# ESP-MGMT.net
KiCad netlist of a schematic drawn in Altium Designer
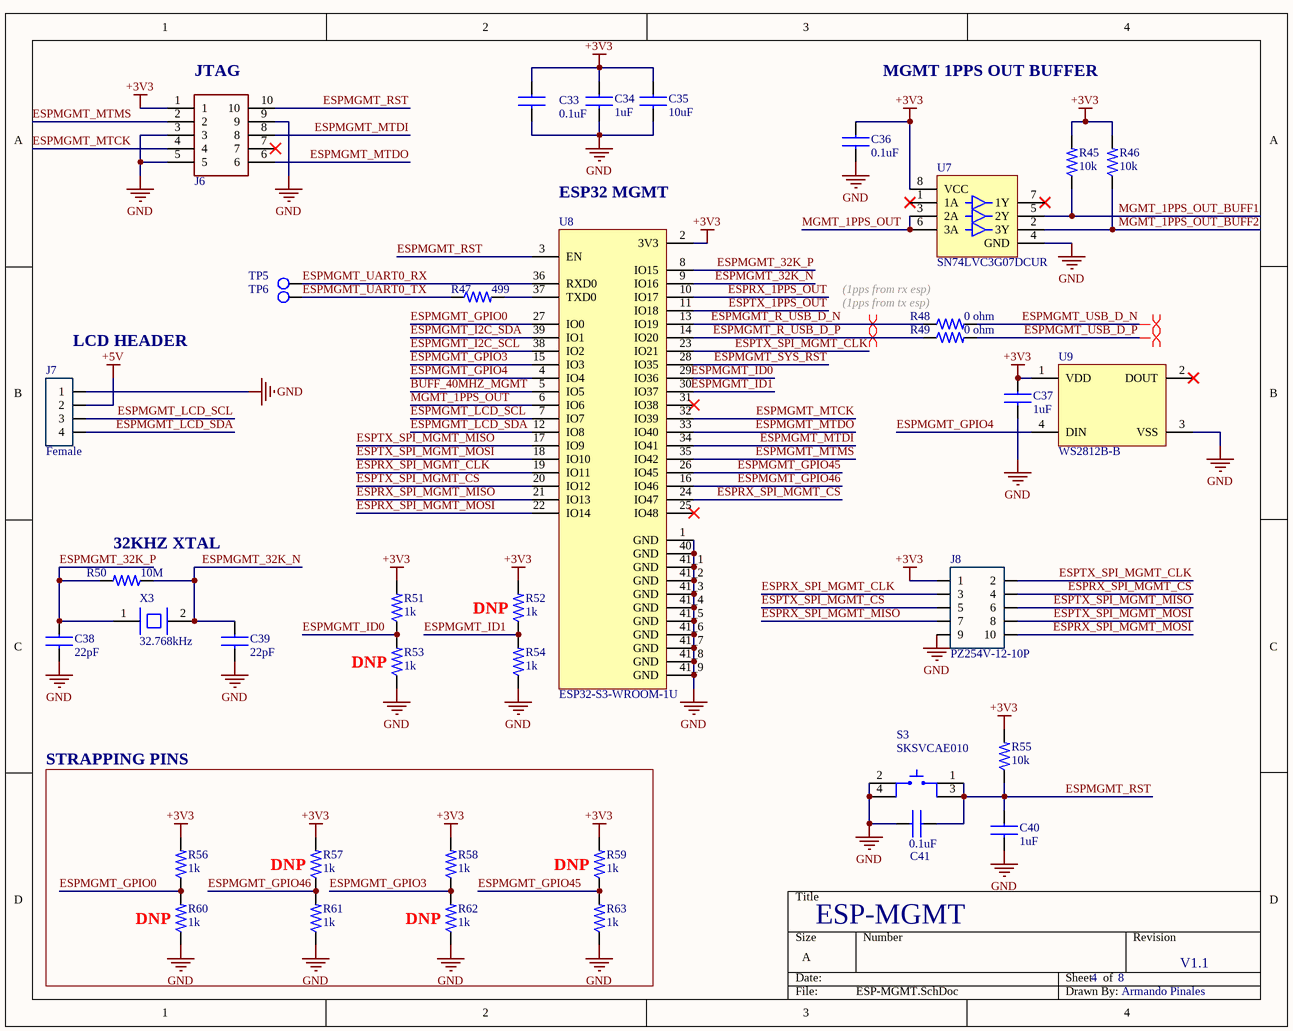
[diagram p0: ESP-MGMT.SchDoc]

(export (version "E")
  (design (tool "Eeschema 10.0.6"))
  (components
    (comp (ref "C33")
      (value "0.1uF")
      (footprint "CAP_0402")
      (description "Cap Ceramic 0.1uF 16V X7R 10% SMD 0402 125C Paper T/R")
      (fields
        (field (name "MANUFACTURER") "Murata")
        (field (name "MANUFACTURER PART NUMBER") "GCM155R71C104KA55J")
      )
      (libsource (lib "LotusSound") (part "CAP_GCM155R71C104KA55J"))
    )
    (comp (ref "C34")
      (value "1uF")
      (footprint "CAP_0402")
      (description "Cap Ceramic 1uF 25V X5R 10% SMD 0402 85°C Cardboard T/R")
      (fields
        (field (name "MANUFACTURER") "Samsung")
        (field (name "MANUFACTURER PART NUMBER") "CL05A105KA5NQNC")
      )
      (libsource (lib "LotusSound") (part "CAP_CL05A105KA5NQNC"))
    )
    (comp (ref "C35")
      (value "10uF")
      (footprint "CAP_0402")
      (description "Cap Ceramic 10uF 6.3V X5R 20% SMD 0402 85°C Paper T/R")
      (fields
        (field (name "MANUFACTURER") "Samsung")
        (field (name "MANUFACTURER PART NUMBER") "CL05A106MQ5NUNC")
      )
      (libsource (lib "LotusSound") (part "CAP_CL05A106MQ5NUNC"))
    )
    (comp (ref "C36")
      (value "0.1uF")
      (footprint "CAP_0402")
      (description "Cap Ceramic 0.1uF 16V X7R 10% SMD 0402 125C Paper T/R")
      (fields
        (field (name "MANUFACTURER") "Murata")
        (field (name "MANUFACTURER PART NUMBER") "GCM155R71C104KA55J")
      )
      (libsource (lib "LotusSound") (part "CAP_GCM155R71C104KA55J"))
    )
    (comp (ref "C37")
      (value "1uF")
      (footprint "CAP_0402")
      (description "Cap Ceramic 1uF 25V X5R 10% SMD 0402 85°C Cardboard T/R")
      (fields
        (field (name "MANUFACTURER") "Samsung")
        (field (name "MANUFACTURER PART NUMBER") "CL05A105KA5NQNC")
      )
      (libsource (lib "LotusSound") (part "CAP_CL05A105KA5NQNC"))
    )
    (comp (ref "C38")
      (value "22pF")
      (footprint "CAP_0402")
      (description "0402 22 pF 50 V ±5 % Tolerance NP0 SMT Multilayer Ceramic Capacitor")
      (fields
        (field (name "MANUFACTURER") "Yageo")
        (field (name "MANUFACTURER PART NUMBER") "CC0402JRNPO9BN220")
      )
      (libsource (lib "LotusSound") (part "CAP_CC0402JRNPO9BN220"))
    )
    (comp (ref "C39")
      (value "22pF")
      (footprint "CAP_0402")
      (description "0402 22 pF 50 V ±5 % Tolerance NP0 SMT Multilayer Ceramic Capacitor")
      (fields
        (field (name "MANUFACTURER") "Yageo")
        (field (name "MANUFACTURER PART NUMBER") "CC0402JRNPO9BN220")
      )
      (libsource (lib "LotusSound") (part "CAP_CC0402JRNPO9BN220"))
    )
    (comp (ref "C40")
      (value "1uF")
      (footprint "CAP_0402")
      (description "Cap Ceramic 1uF 25V X5R 10% SMD 0402 85°C Cardboard T/R")
      (fields
        (field (name "MANUFACTURER") "Samsung")
        (field (name "MANUFACTURER PART NUMBER") "CL05A105KA5NQNC")
      )
      (libsource (lib "LotusSound") (part "CAP_CL05A105KA5NQNC"))
    )
    (comp (ref "C41")
      (value "0.1uF")
      (footprint "CAP_0402")
      (description "Cap Ceramic 0.1uF 16V X7R 10% SMD 0402 125C Paper T/R")
      (fields
        (field (name "MANUFACTURER") "Murata")
        (field (name "MANUFACTURER PART NUMBER") "GCM155R71C104KA55J")
      )
      (libsource (lib "LotusSound") (part "CAP_GCM155R71C104KA55J"))
    )
    (comp (ref "J6")
      (value "CONN_TC2050-IDC")
      (footprint "CONN_TAG-CONNECT_TC2050-IDC")
      (description "Cbl Plug-Of-Nails 10-Pin w/Legs")
      (fields (field (name "MF") "{'manufacturer': u'Tag-Connect LLC'}") (field (name "MP") "TC2050-IDC"))
      (libsource (lib "LotusSound") (part "CONN_TC2050-IDC"))
    )
    (comp (ref "J7")
      (value "Female")
      (footprint "CONN_4_PIN_100MIL")
      (description "4 Position Header Connector 0.100\" (2.54mm) Through Hole Tin")
      (fields (field (name "DIGIKEY PART") "S7004-ND") (field (name "LCSC PART#") "DNP"))
      (libsource (lib "LotusSound") (part "CONN_4_PIN_FEMALE"))
    )
    (comp (ref "J8")
      (value "PZ254V-12-10P")
      (footprint "CONN_10_PIN_M_100MIL")
      (description "双排排针 间距2.54mm 10pin 直插")
      (fields (field (name "MANUFACTURER") "XFCN"))
      (libsource (lib "LotusSound") (part "CONN_10_PIN_MALE_PZ254V-12-10P"))
    )
    (comp (ref "R45")
      (value "10k")
      (footprint "RES_0402")
      (description "RES SMD 10K OHM 1% 1/16W 0402")
      (fields
        (field (name "MANUFACTURER") "Yageo")
        (field (name "MANUFACTURER PART NUMBER") "AC0402FR-0710KL")
      )
      (libsource (lib "LotusSound") (part "RES_AC0402FR-0710KL"))
    )
    (comp (ref "R46")
      (value "10k")
      (footprint "RES_0402")
      (description "RES SMD 10K OHM 1% 1/16W 0402")
      (fields
        (field (name "MANUFACTURER") "Yageo")
        (field (name "MANUFACTURER PART NUMBER") "AC0402FR-0710KL")
      )
      (libsource (lib "LotusSound") (part "RES_AC0402FR-0710KL"))
    )
    (comp (ref "R47")
      (value "499")
      (footprint "RES_0402")
      (description "Res General Purpose Thick Film 0402 499 Ohm 1% 1/16W ±100ppm/°C Molded SMD Paper T/R")
      (fields
        (field (name "MANUFACTURER") "Yageo")
        (field (name "MANUFACTURER PART NUMBER") "RC0402FR-07499RL")
      )
      (libsource (lib "LotusSound") (part "RES_RC0402FR-07499RL"))
    )
    (comp (ref "R48")
      (value "0 ohm")
      (footprint "RES_0402")
      (description "RES SMD 0 OHM JUMPER 1/16W 0402")
      (fields
        (field (name "MANUFACTURER") "Yageo")
        (field (name "MANUFACTURER PART NUMBER") "RC0402JR-070RL")
      )
      (libsource (lib "LotusSound") (part "RES_RC0402JR-070RL"))
    )
    (comp (ref "R49")
      (value "0 ohm")
      (footprint "RES_0402")
      (description "RES SMD 0 OHM JUMPER 1/16W 0402")
      (fields
        (field (name "MANUFACTURER") "Yageo")
        (field (name "MANUFACTURER PART NUMBER") "RC0402JR-070RL")
      )
      (libsource (lib "LotusSound") (part "RES_RC0402JR-070RL"))
    )
    (comp (ref "R50")
      (value "10M")
      (footprint "RES_0402")
      (description "Res Thick Film 0402 10M Ohm 5% 0.063W(1/16W) ±100ppm/C Pad SMD Automotive T/R")
      (fields
        (field (name "MANUFACTURER") "TE Connectivity")
        (field (name "MANUFACTURER PART NUMBER") "CRGCQ0402J10M")
      )
      (libsource (lib "LotusSound") (part "RES_CRGCQ0402J10M"))
    )
    (comp (ref "R51")
      (value "1k")
      (footprint "RES_0402")
      (description "Res General Purpose Thick Film 0402 1K Ohm 5% 1/16W ±100ppm/°C Molded SMD Paper T/R")
      (fields
        (field (name "MANUFACTURER") "Yageo")
        (field (name "MANUFACTURER PART NUMBER") "RC0402JR-071KL")
      )
      (libsource (lib "LotusSound") (part "RES_RC0402JR-071KL"))
    )
    (comp (ref "R52")
      (value "1k")
      (footprint "RES_0402")
      (description "Res General Purpose Thick Film 0402 1K Ohm 5% 1/16W ±100ppm/°C Molded SMD Paper T/R")
      (fields
        (field (name "MANUFACTURER") "Yageo")
        (field (name "MANUFACTURER PART NUMBER") "RC0402JR-071KL")
      )
      (libsource (lib "LotusSound") (part "RES_RC0402JR-071KL"))
    )
    (comp (ref "R53")
      (value "1k")
      (footprint "RES_0402")
      (description "Res General Purpose Thick Film 0402 1K Ohm 5% 1/16W ±100ppm/°C Molded SMD Paper T/R")
      (fields
        (field (name "MANUFACTURER") "Yageo")
        (field (name "MANUFACTURER PART NUMBER") "RC0402JR-071KL")
      )
      (libsource (lib "LotusSound") (part "RES_RC0402JR-071KL"))
    )
    (comp (ref "R54")
      (value "1k")
      (footprint "RES_0402")
      (description "Res General Purpose Thick Film 0402 1K Ohm 5% 1/16W ±100ppm/°C Molded SMD Paper T/R")
      (fields
        (field (name "MANUFACTURER") "Yageo")
        (field (name "MANUFACTURER PART NUMBER") "RC0402JR-071KL")
      )
      (libsource (lib "LotusSound") (part "RES_RC0402JR-071KL"))
    )
    (comp (ref "R55")
      (value "10k")
      (footprint "RES_0402")
      (description "RES SMD 10K OHM 1% 1/16W 0402")
      (fields
        (field (name "MANUFACTURER") "Yageo")
        (field (name "MANUFACTURER PART NUMBER") "AC0402FR-0710KL")
      )
      (libsource (lib "LotusSound") (part "RES_AC0402FR-0710KL"))
    )
    (comp (ref "R56")
      (value "1k")
      (footprint "RES_0402")
      (description "Res General Purpose Thick Film 0402 1K Ohm 5% 1/16W ±100ppm/°C Molded SMD Paper T/R")
      (fields
        (field (name "MANUFACTURER") "Yageo")
        (field (name "MANUFACTURER PART NUMBER") "RC0402JR-071KL")
      )
      (libsource (lib "LotusSound") (part "RES_RC0402JR-071KL"))
    )
    (comp (ref "R57")
      (value "1k")
      (footprint "RES_0402")
      (description "Res General Purpose Thick Film 0402 1K Ohm 5% 1/16W ±100ppm/°C Molded SMD Paper T/R")
      (fields
        (field (name "MANUFACTURER") "Yageo")
        (field (name "MANUFACTURER PART NUMBER") "RC0402JR-071KL")
      )
      (libsource (lib "LotusSound") (part "RES_RC0402JR-071KL"))
    )
    (comp (ref "R58")
      (value "1k")
      (footprint "RES_0402")
      (description "Res General Purpose Thick Film 0402 1K Ohm 5% 1/16W ±100ppm/°C Molded SMD Paper T/R")
      (fields
        (field (name "MANUFACTURER") "Yageo")
        (field (name "MANUFACTURER PART NUMBER") "RC0402JR-071KL")
      )
      (libsource (lib "LotusSound") (part "RES_RC0402JR-071KL"))
    )
    (comp (ref "R59")
      (value "1k")
      (footprint "RES_0402")
      (description "Res General Purpose Thick Film 0402 1K Ohm 5% 1/16W ±100ppm/°C Molded SMD Paper T/R")
      (fields
        (field (name "MANUFACTURER") "Yageo")
        (field (name "MANUFACTURER PART NUMBER") "RC0402JR-071KL")
      )
      (libsource (lib "LotusSound") (part "RES_RC0402JR-071KL"))
    )
    (comp (ref "R60")
      (value "1k")
      (footprint "RES_0402")
      (description "Res General Purpose Thick Film 0402 1K Ohm 5% 1/16W ±100ppm/°C Molded SMD Paper T/R")
      (fields
        (field (name "MANUFACTURER") "Yageo")
        (field (name "MANUFACTURER PART NUMBER") "RC0402JR-071KL")
      )
      (libsource (lib "LotusSound") (part "RES_RC0402JR-071KL"))
    )
    (comp (ref "R61")
      (value "1k")
      (footprint "RES_0402")
      (description "Res General Purpose Thick Film 0402 1K Ohm 5% 1/16W ±100ppm/°C Molded SMD Paper T/R")
      (fields
        (field (name "MANUFACTURER") "Yageo")
        (field (name "MANUFACTURER PART NUMBER") "RC0402JR-071KL")
      )
      (libsource (lib "LotusSound") (part "RES_RC0402JR-071KL"))
    )
    (comp (ref "R62")
      (value "1k")
      (footprint "RES_0402")
      (description "Res General Purpose Thick Film 0402 1K Ohm 5% 1/16W ±100ppm/°C Molded SMD Paper T/R")
      (fields
        (field (name "MANUFACTURER") "Yageo")
        (field (name "MANUFACTURER PART NUMBER") "RC0402JR-071KL")
      )
      (libsource (lib "LotusSound") (part "RES_RC0402JR-071KL"))
    )
    (comp (ref "R63")
      (value "1k")
      (footprint "RES_0402")
      (description "Res General Purpose Thick Film 0402 1K Ohm 5% 1/16W ±100ppm/°C Molded SMD Paper T/R")
      (fields
        (field (name "MANUFACTURER") "Yageo")
        (field (name "MANUFACTURER PART NUMBER") "RC0402JR-071KL")
      )
      (libsource (lib "LotusSound") (part "RES_RC0402JR-071KL"))
    )
    (comp (ref "S3")
      (value "SKSVCAE010")
      (footprint "SW_SKSVCAE010")
      (description "2.8x1.9mm Compact Type with Projection Surface Mount SKSV Series Tact Switch")
      (fields (field (name "MANUFACTURER") "Alps Electric"))
      (libsource (lib "LotusSound") (part "SW_SKSVCAE010"))
    )
    (comp (ref "TP5")
      (value "Test Point 1MM")
      (footprint "TP_PAD-1MM")
      (libsource (lib "LotusSound") (part "TP_PAD-1MM"))
    )
    (comp (ref "TP6")
      (value "Test Point 1MM")
      (footprint "TP_PAD-1MM")
      (libsource (lib "LotusSound") (part "TP_PAD-1MM"))
    )
    (comp (ref "U7")
      (value "SN74LVC3G07DCUR")
      (footprint "IC_SN74LVC3G07DCUR")
      (description "Triple Buffer/Driver With Open-Drain Output, DCU0008A, LARGE T&R")
      (fields
        (field (name "GENERIC PART NUMBER") "SN74LVC3G07")
        (field (name "MANUFACTURER") "Texas Instruments")
      )
      (libsource (lib "LotusSound") (part "IC_SN74LVC3G07DCUR"))
    )
    (comp (ref "U8")
      (value "ESP32-S3-WROOM-1U")
      (footprint "IC_ESP32-S3-WROOM-1U")
      (description "2.4 GHz Wi-Fi (802.11 b/g/n) and Bluetooth 5 (LE) module")
      (fields (field (name "MF") "Espressif Systems"))
      (libsource (lib "LotusSound") (part "IC_ESP32-S3-WROOM-1U"))
    )
    (comp (ref "U9")
      (value "WS2812B-B")
      (footprint "LED_WS2812B-B")
      (description "Intelligent control LED integrated light source")
      (fields
        (field (name "MANUFACTURER") "WORLDSEMI")
        (field (name "MANUFACTURER PART NUMBER") "WS2812B-B/W")
      )
      (libsource (lib "LotusSound") (part "LED_WS2812B-B"))
    )
    (comp (ref "X3")
      (value "32.768kHz")
      (footprint "XTAL_X321532768KGD2SI")
      (description "贴片无源晶振 32.768KHZ 12.5PF ±20ppm –40~+85 ℃")
      (fields
        (field (name "MANUFACTURER") "YXC")
        (field (name "MANUFACTURER PART NUMBER") "X321532768KGD2SI")
      )
      (libsource (lib "LotusSound") (part "XTAL_X321532768KGD2SI"))
    )
  )
  (nets
    (net (code "1") (name "+3V3") (class "Default")
      (node (ref "C33") (pin "2") (pinfunction "2_2") (pintype "passive"))
      (node (ref "C34") (pin "2") (pinfunction "2_2") (pintype "passive"))
      (node (ref "C35") (pin "2") (pinfunction "2_2") (pintype "passive"))
      (node (ref "C36") (pin "2") (pinfunction "2_2") (pintype "passive"))
      (node (ref "C37") (pin "2") (pinfunction "2_2") (pintype "passive"))
      (node (ref "J6") (pin "1") (pinfunction "1_1") (pintype "passive"))
      (node (ref "J8") (pin "1") (pinfunction "1_1") (pintype "passive"))
      (node (ref "R45") (pin "2") (pinfunction "2_2") (pintype "passive"))
      (node (ref "R46") (pin "2") (pinfunction "2_2") (pintype "passive"))
      (node (ref "R51") (pin "2") (pinfunction "2_2") (pintype "passive"))
      (node (ref "R52") (pin "2") (pinfunction "2_2") (pintype "passive"))
      (node (ref "R55") (pin "2") (pinfunction "2_2") (pintype "passive"))
      (node (ref "R56") (pin "2") (pinfunction "2_2") (pintype "passive"))
      (node (ref "R57") (pin "2") (pinfunction "2_2") (pintype "passive"))
      (node (ref "R58") (pin "2") (pinfunction "2_2") (pintype "passive"))
      (node (ref "R59") (pin "2") (pinfunction "2_2") (pintype "passive"))
      (node (ref "U7") (pin "8") (pinfunction "VCC_8") (pintype "passive"))
      (node (ref "U8") (pin "2") (pinfunction "3V3_2") (pintype "passive"))
      (node (ref "U9") (pin "1") (pinfunction "VDD_1") (pintype "power_in"))
    )
    (net (code "2") (name "+5V") (class "Default")
      (node (ref "J7") (pin "2") (pinfunction "2_2") (pintype "passive"))
    )
    (net (code "3") (name "/BUFF_40MHZ_MGMT") (class "Default")
      (node (ref "U8") (pin "5") (pinfunction "IO5_5") (pintype "passive"))
    )
    (net (code "4") (name "/ESPMGMT_32K_N") (class "Default")
      (node (ref "C39") (pin "2") (pinfunction "2_2") (pintype "passive"))
      (node (ref "R50") (pin "1") (pinfunction "1_1") (pintype "passive"))
      (node (ref "U8") (pin "9") (pinfunction "IO16_9") (pintype "passive"))
      (node (ref "X3") (pin "2") (pinfunction "GND_2") (pintype "power_in"))
    )
    (net (code "5") (name "/ESPMGMT_32K_P") (class "Default")
      (node (ref "C38") (pin "2") (pinfunction "2_2") (pintype "passive"))
      (node (ref "R50") (pin "2") (pinfunction "2_2") (pintype "passive"))
      (node (ref "U8") (pin "8") (pinfunction "IO15_8") (pintype "passive"))
      (node (ref "X3") (pin "1") (pinfunction "IN/OUT_1") (pintype "passive"))
    )
    (net (code "6") (name "/ESPMGMT_GPIO0") (class "Default")
      (node (ref "R56") (pin "1") (pinfunction "1_1") (pintype "passive"))
      (node (ref "R60") (pin "2") (pinfunction "2_2") (pintype "passive"))
      (node (ref "U8") (pin "27") (pinfunction "IO0_27") (pintype "passive"))
    )
    (net (code "7") (name "/ESPMGMT_GPIO3") (class "Default")
      (node (ref "R58") (pin "1") (pinfunction "1_1") (pintype "passive"))
      (node (ref "R62") (pin "2") (pinfunction "2_2") (pintype "passive"))
      (node (ref "U8") (pin "15") (pinfunction "IO3_15") (pintype "passive"))
    )
    (net (code "8") (name "/ESPMGMT_GPIO4") (class "Default")
      (node (ref "U8") (pin "4") (pinfunction "IO4_4") (pintype "passive"))
      (node (ref "U9") (pin "4") (pinfunction "DIN_4") (pintype "passive"))
    )
    (net (code "9") (name "/ESPMGMT_GPIO45") (class "Default")
      (node (ref "R59") (pin "1") (pinfunction "1_1") (pintype "passive"))
      (node (ref "R63") (pin "2") (pinfunction "2_2") (pintype "passive"))
      (node (ref "U8") (pin "26") (pinfunction "IO45_26") (pintype "passive"))
    )
    (net (code "10") (name "/ESPMGMT_GPIO46") (class "Default")
      (node (ref "R57") (pin "1") (pinfunction "1_1") (pintype "passive"))
      (node (ref "R61") (pin "2") (pinfunction "2_2") (pintype "passive"))
      (node (ref "U8") (pin "16") (pinfunction "IO46_16") (pintype "passive"))
    )
    (net (code "11") (name "/ESPMGMT_I2C_SCL") (class "Default")
      (node (ref "U8") (pin "38") (pinfunction "IO2_38") (pintype "passive"))
    )
    (net (code "12") (name "/ESPMGMT_I2C_SDA") (class "Default")
      (node (ref "U8") (pin "39") (pinfunction "IO1_39") (pintype "passive"))
    )
    (net (code "13") (name "/ESPMGMT_ID0") (class "Default")
      (node (ref "R51") (pin "1") (pinfunction "1_1") (pintype "passive"))
      (node (ref "R53") (pin "2") (pinfunction "2_2") (pintype "passive"))
      (node (ref "U8") (pin "29") (pinfunction "IO36_29") (pintype "passive"))
    )
    (net (code "14") (name "/ESPMGMT_ID1") (class "Default")
      (node (ref "R52") (pin "1") (pinfunction "1_1") (pintype "passive"))
      (node (ref "R54") (pin "2") (pinfunction "2_2") (pintype "passive"))
      (node (ref "U8") (pin "30") (pinfunction "IO37_30") (pintype "passive"))
    )
    (net (code "15") (name "/ESPMGMT_LCD_SCL") (class "Default")
      (node (ref "J7") (pin "3") (pinfunction "3_3") (pintype "passive"))
      (node (ref "U8") (pin "7") (pinfunction "IO7_7") (pintype "passive"))
    )
    (net (code "16") (name "/ESPMGMT_LCD_SDA") (class "Default")
      (node (ref "J7") (pin "4") (pinfunction "4_4") (pintype "passive"))
      (node (ref "U8") (pin "12") (pinfunction "IO8_12") (pintype "passive"))
    )
    (net (code "17") (name "/ESPMGMT_MTCK") (class "Default")
      (node (ref "J6") (pin "4") (pinfunction "4_4") (pintype "passive"))
      (node (ref "U8") (pin "32") (pinfunction "IO39_32") (pintype "passive"))
    )
    (net (code "18") (name "/ESPMGMT_MTDI") (class "Default")
      (node (ref "J6") (pin "8") (pinfunction "8_8") (pintype "passive"))
      (node (ref "U8") (pin "34") (pinfunction "IO41_34") (pintype "passive"))
    )
    (net (code "19") (name "/ESPMGMT_MTDO") (class "Default")
      (node (ref "J6") (pin "6") (pinfunction "6_6") (pintype "passive"))
      (node (ref "U8") (pin "33") (pinfunction "IO40_33") (pintype "passive"))
    )
    (net (code "20") (name "/ESPMGMT_MTMS") (class "Default")
      (node (ref "J6") (pin "2") (pinfunction "2_2") (pintype "passive"))
      (node (ref "U8") (pin "35") (pinfunction "IO42_35") (pintype "passive"))
    )
    (net (code "21") (name "/ESPMGMT_RST") (class "Default")
      (node (ref "C40") (pin "2") (pinfunction "2_2") (pintype "passive"))
      (node (ref "C41") (pin "2") (pinfunction "2_2") (pintype "passive"))
      (node (ref "J6") (pin "10") (pinfunction "10_10") (pintype "passive"))
      (node (ref "R55") (pin "1") (pinfunction "1_1") (pintype "passive"))
      (node (ref "S3") (pin "1") (pinfunction "1_1") (pintype "passive"))
      (node (ref "S3") (pin "3") (pinfunction "3_3") (pintype "passive"))
      (node (ref "U8") (pin "3") (pinfunction "EN_3") (pintype "passive"))
    )
    (net (code "22") (name "/ESPMGMT_R_USB_D_N") (class "Default")
      (node (ref "R48") (pin "1") (pinfunction "1_1") (pintype "passive"))
      (node (ref "U8") (pin "13") (pinfunction "IO19_13") (pintype "passive"))
    )
    (net (code "23") (name "/ESPMGMT_R_USB_D_P") (class "Default")
      (node (ref "R49") (pin "1") (pinfunction "1_1") (pintype "passive"))
      (node (ref "U8") (pin "14") (pinfunction "IO20_14") (pintype "passive"))
    )
    (net (code "24") (name "/ESPMGMT_SYS_RST") (class "Default")
      (node (ref "U8") (pin "28") (pinfunction "IO35_28") (pintype "passive"))
    )
    (net (code "25") (name "/ESPMGMT_UART0_RX") (class "Default")
      (node (ref "TP5") (pin "1") (pinfunction "1_1") (pintype "passive"))
      (node (ref "U8") (pin "36") (pinfunction "RXD0_36") (pintype "passive"))
    )
    (net (code "26") (name "/ESPMGMT_UART0_TX") (class "Default")
      (node (ref "R47") (pin "1") (pinfunction "1_1") (pintype "passive"))
      (node (ref "TP6") (pin "1") (pinfunction "1_1") (pintype "passive"))
    )
    (net (code "27") (name "/ESPMGMT_USB_D_N") (class "Default")
      (node (ref "R48") (pin "2") (pinfunction "2_2") (pintype "passive"))
    )
    (net (code "28") (name "/ESPMGMT_USB_D_P") (class "Default")
      (node (ref "R49") (pin "2") (pinfunction "2_2") (pintype "passive"))
    )
    (net (code "29") (name "/ESPRX_1PPS_OUT") (class "Default")
      (node (ref "U8") (pin "10") (pinfunction "IO17_10") (pintype "passive"))
    )
    (net (code "30") (name "/ESPRX_SPI_MGMT_CLK") (class "Default")
      (node (ref "J8") (pin "3") (pinfunction "3_3") (pintype "passive"))
      (node (ref "U8") (pin "19") (pinfunction "IO11_19") (pintype "passive"))
    )
    (net (code "31") (name "/ESPRX_SPI_MGMT_CS") (class "Default")
      (node (ref "J8") (pin "4") (pinfunction "4_4") (pintype "passive"))
      (node (ref "U8") (pin "24") (pinfunction "IO47_24") (pintype "passive"))
    )
    (net (code "32") (name "/ESPRX_SPI_MGMT_MISO") (class "Default")
      (node (ref "J8") (pin "7") (pinfunction "7_7") (pintype "passive"))
      (node (ref "U8") (pin "21") (pinfunction "IO13_21") (pintype "passive"))
    )
    (net (code "33") (name "/ESPRX_SPI_MGMT_MOSI") (class "Default")
      (node (ref "J8") (pin "10") (pinfunction "10_10") (pintype "passive"))
      (node (ref "U8") (pin "22") (pinfunction "IO14_22") (pintype "passive"))
    )
    (net (code "34") (name "/ESPTX_1PPS_OUT") (class "Default")
      (node (ref "U8") (pin "11") (pinfunction "IO18_11") (pintype "passive"))
    )
    (net (code "35") (name "/ESPTX_SPI_MGMT_CLK") (class "Default")
      (node (ref "J8") (pin "2") (pinfunction "2_2") (pintype "passive"))
      (node (ref "U8") (pin "23") (pinfunction "IO21_23") (pintype "passive"))
    )
    (net (code "36") (name "/ESPTX_SPI_MGMT_CS") (class "Default")
      (node (ref "J8") (pin "5") (pinfunction "5_5") (pintype "passive"))
      (node (ref "U8") (pin "20") (pinfunction "IO12_20") (pintype "passive"))
    )
    (net (code "37") (name "/ESPTX_SPI_MGMT_MISO") (class "Default")
      (node (ref "J8") (pin "6") (pinfunction "6_6") (pintype "passive"))
      (node (ref "U8") (pin "17") (pinfunction "IO9_17") (pintype "passive"))
    )
    (net (code "38") (name "/ESPTX_SPI_MGMT_MOSI") (class "Default")
      (node (ref "J8") (pin "8") (pinfunction "8_8") (pintype "passive"))
      (node (ref "U8") (pin "18") (pinfunction "IO10_18") (pintype "passive"))
    )
    (net (code "39") (name "/MGMT_1PPS_OUT") (class "Default")
      (node (ref "U7") (pin "3") (pinfunction "2A_3") (pintype "passive"))
      (node (ref "U7") (pin "6") (pinfunction "3A_6") (pintype "passive"))
      (node (ref "U8") (pin "6") (pinfunction "IO6_6") (pintype "passive"))
    )
    (net (code "40") (name "/MGMT_1PPS_OUT_BUFF1") (class "Default")
      (node (ref "R45") (pin "1") (pinfunction "1_1") (pintype "passive"))
      (node (ref "U7") (pin "5") (pinfunction "2Y_5") (pintype "passive"))
    )
    (net (code "41") (name "/MGMT_1PPS_OUT_BUFF2") (class "Default")
      (node (ref "R46") (pin "1") (pinfunction "1_1") (pintype "passive"))
      (node (ref "U7") (pin "2") (pinfunction "3Y_2") (pintype "passive"))
    )
    (net (code "42") (name "GND") (class "Default")
      (node (ref "C33") (pin "1") (pinfunction "1_1") (pintype "passive"))
      (node (ref "C34") (pin "1") (pinfunction "1_1") (pintype "passive"))
      (node (ref "C35") (pin "1") (pinfunction "1_1") (pintype "passive"))
      (node (ref "C36") (pin "1") (pinfunction "1_1") (pintype "passive"))
      (node (ref "C37") (pin "1") (pinfunction "1_1") (pintype "passive"))
      (node (ref "C38") (pin "1") (pinfunction "1_1") (pintype "passive"))
      (node (ref "C39") (pin "1") (pinfunction "1_1") (pintype "passive"))
      (node (ref "C40") (pin "1") (pinfunction "1_1") (pintype "passive"))
      (node (ref "C41") (pin "1") (pinfunction "1_1") (pintype "passive"))
      (node (ref "J6") (pin "3") (pinfunction "3_3") (pintype "passive"))
      (node (ref "J6") (pin "5") (pinfunction "5_5") (pintype "passive"))
      (node (ref "J6") (pin "9") (pinfunction "9_9") (pintype "passive"))
      (node (ref "J7") (pin "1") (pinfunction "1_1") (pintype "passive"))
      (node (ref "J8") (pin "9") (pinfunction "9_9") (pintype "passive"))
      (node (ref "R53") (pin "1") (pinfunction "1_1") (pintype "passive"))
      (node (ref "R54") (pin "1") (pinfunction "1_1") (pintype "passive"))
      (node (ref "R60") (pin "1") (pinfunction "1_1") (pintype "passive"))
      (node (ref "R61") (pin "1") (pinfunction "1_1") (pintype "passive"))
      (node (ref "R62") (pin "1") (pinfunction "1_1") (pintype "passive"))
      (node (ref "R63") (pin "1") (pinfunction "1_1") (pintype "passive"))
      (node (ref "S3") (pin "2") (pinfunction "2_2") (pintype "passive"))
      (node (ref "S3") (pin "4") (pinfunction "4_4") (pintype "passive"))
      (node (ref "U7") (pin "4") (pinfunction "GND_4") (pintype "passive"))
      (node (ref "U8") (pin "1") (pinfunction "GND_1") (pintype "passive"))
      (node (ref "U8") (pin "40") (pinfunction "GND_40") (pintype "passive"))
      (node (ref "U8") (pin "41_1") (pinfunction "GND_41_1") (pintype "passive"))
      (node (ref "U8") (pin "41_2") (pinfunction "GND_41_2") (pintype "passive"))
      (node (ref "U8") (pin "41_3") (pinfunction "GND_41_3") (pintype "passive"))
      (node (ref "U8") (pin "41_4") (pinfunction "GND_41_4") (pintype "passive"))
      (node (ref "U8") (pin "41_5") (pinfunction "GND_41_5") (pintype "passive"))
      (node (ref "U8") (pin "41_6") (pinfunction "GND_41_6") (pintype "passive"))
      (node (ref "U8") (pin "41_7") (pinfunction "GND_41_7") (pintype "passive"))
      (node (ref "U8") (pin "41_8") (pinfunction "GND_41_8") (pintype "passive"))
      (node (ref "U8") (pin "41_9") (pinfunction "GND_41_9") (pintype "passive"))
      (node (ref "U9") (pin "3") (pinfunction "VSS_3") (pintype "power_in"))
    )
    (net (code "43") (name "Net-(U8-TXD0)") (class "Default")
      (node (ref "R47") (pin "2") (pinfunction "2_2") (pintype "passive"))
      (node (ref "U8") (pin "37") (pinfunction "TXD0_37") (pintype "passive"))
    )
    (net (code "44") (name "unconnected-(J6-Pad7)") (class "Default")
      (node (ref "J6") (pin "7") (pinfunction "7_7") (pintype "passive+no_connect"))
    )
    (net (code "45") (name "unconnected-(U7-1A-Pad1)") (class "Default")
      (node (ref "U7") (pin "1") (pinfunction "1A_1") (pintype "passive+no_connect"))
    )
    (net (code "46") (name "unconnected-(U7-1Y-Pad7)") (class "Default")
      (node (ref "U7") (pin "7") (pinfunction "1Y_7") (pintype "passive+no_connect"))
    )
    (net (code "47") (name "unconnected-(U8-IO38-Pad31)") (class "Default")
      (node (ref "U8") (pin "31") (pinfunction "IO38_31") (pintype "passive+no_connect"))
    )
    (net (code "48") (name "unconnected-(U8-IO48-Pad25)") (class "Default")
      (node (ref "U8") (pin "25") (pinfunction "IO48_25") (pintype "passive+no_connect"))
    )
    (net (code "49") (name "unconnected-(U9-DOUT-Pad2)") (class "Default")
      (node (ref "U9") (pin "2") (pinfunction "DOUT_2") (pintype "passive+no_connect"))
    )
  )
)
